# CAN-Adapter.net
KiCad netlist of a schematic drawn in EAGLE
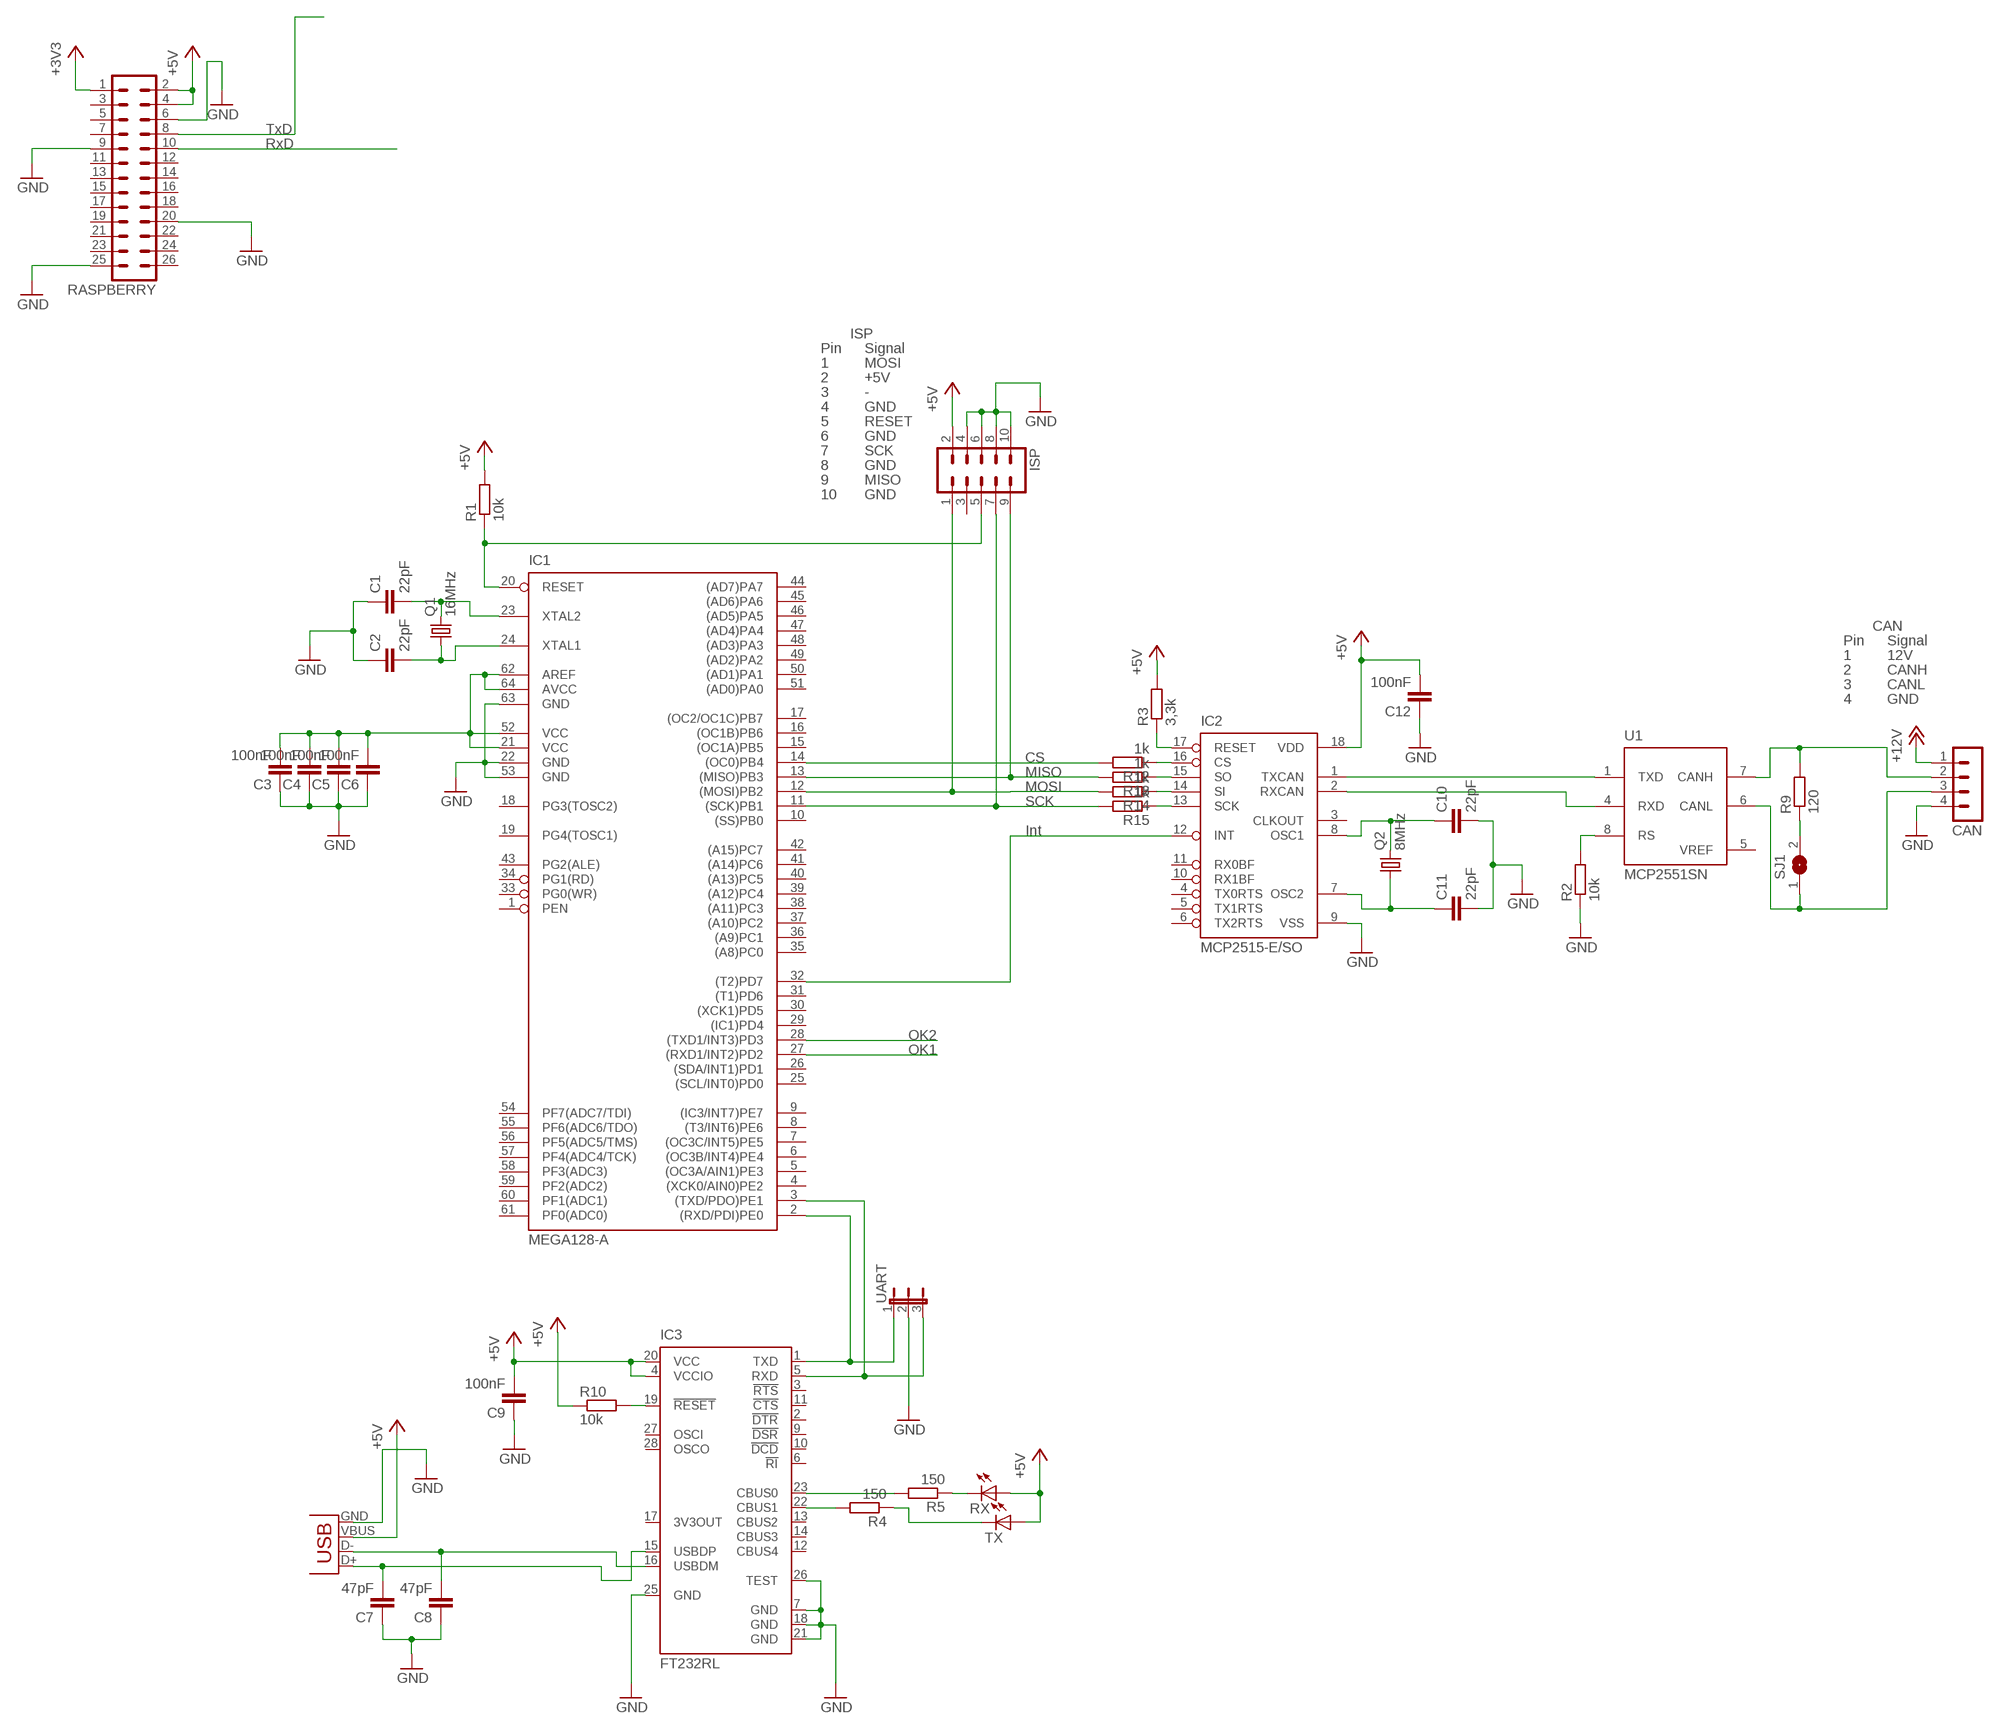
[diagram p0: schematic, sheet 1]

(export (version "E")
  (design (tool "Eeschema 10.0.6"))
  (components
    (comp (ref "C1")
      (value "22pF")
      (footprint "eagle-import:C0805")
      (libsource (lib "eagle-import") (part "C-EUC0805"))
    )
    (comp (ref "C2")
      (value "22pF")
      (footprint "eagle-import:C0805")
      (libsource (lib "eagle-import") (part "C-EUC0805"))
    )
    (comp (ref "C3")
      (value "100nF")
      (footprint "eagle-import:C0805")
      (libsource (lib "eagle-import") (part "C-EUC0805"))
    )
    (comp (ref "C4")
      (value "100nF")
      (footprint "eagle-import:C0805")
      (libsource (lib "eagle-import") (part "C-EUC0805"))
    )
    (comp (ref "C5")
      (value "100nF")
      (footprint "eagle-import:C0805")
      (libsource (lib "eagle-import") (part "C-EUC0805"))
    )
    (comp (ref "C6")
      (value "100nF")
      (footprint "eagle-import:C0805")
      (libsource (lib "eagle-import") (part "C-EUC0805"))
    )
    (comp (ref "C7")
      (value "47pF")
      (footprint "eagle-import:C0805")
      (libsource (lib "eagle-import") (part "C-EUC0805"))
    )
    (comp (ref "C8")
      (value "47pF")
      (footprint "eagle-import:C0805")
      (libsource (lib "eagle-import") (part "C-EUC0805"))
    )
    (comp (ref "C9")
      (value "100nF")
      (footprint "eagle-import:C0805")
      (libsource (lib "eagle-import") (part "C-EUC0805"))
    )
    (comp (ref "C10")
      (value "22pF")
      (footprint "eagle-import:C0805")
      (libsource (lib "eagle-import") (part "C-EUC0805"))
    )
    (comp (ref "C11")
      (value "22pF")
      (footprint "eagle-import:C0805")
      (libsource (lib "eagle-import") (part "C-EUC0805"))
    )
    (comp (ref "C12")
      (value "100nF")
      (footprint "eagle-import:C0805")
      (libsource (lib "eagle-import") (part "C-EUC0805"))
    )
    (comp (ref "CAN")
      (value "MA04-1")
      (footprint "eagle-import:MA04-1")
      (libsource (lib "eagle-import") (part "MA04-1"))
    )
    (comp (ref "IC1")
      (value "MEGA128-A")
      (footprint "eagle-import:TQFP64")
      (fields (field (name "MPN") "ATMEGA128-16AU"))
      (libsource (lib "eagle-import") (part "MEGA128-A"))
    )
    (comp (ref "IC2")
      (value "MCP2515-E/SO")
      (footprint "eagle-import:SO18L")
      (libsource (lib "eagle-import") (part "MCP2515-E/SO"))
    )
    (comp (ref "IC3")
      (value "FT232RL")
      (footprint "eagle-import:SSOP28")
      (libsource (lib "eagle-import") (part "FT232RL"))
    )
    (comp (ref "ISP")
      (value "ML10")
      (footprint "eagle-import:ML10")
      (libsource (lib "eagle-import") (part "ML10"))
    )
    (comp (ref "Q1")
      (value "16MHz")
      (footprint "eagle-import:CSM-7X-DU")
      (libsource (lib "eagle-import") (part "CSM-7X-DU"))
    )
    (comp (ref "Q2")
      (value "8MHz")
      (footprint "eagle-import:HC49UP")
      (libsource (lib "eagle-import") (part "CRYSTALHC49UP"))
    )
    (comp (ref "R1")
      (value "10k")
      (footprint "eagle-import:R0805")
      (libsource (lib "eagle-import") (part "R-EU_R0805"))
    )
    (comp (ref "R2")
      (value "10k")
      (footprint "eagle-import:M0805")
      (libsource (lib "eagle-import") (part "R-EU_M0805"))
    )
    (comp (ref "R3")
      (value "3,3k")
      (footprint "eagle-import:M0805")
      (libsource (lib "eagle-import") (part "R-EU_M0805"))
    )
    (comp (ref "R4")
      (value "150")
      (footprint "eagle-import:M0805")
      (libsource (lib "eagle-import") (part "R-EU_M0805"))
    )
    (comp (ref "R5")
      (value "150")
      (footprint "eagle-import:M0805")
      (libsource (lib "eagle-import") (part "R-EU_M0805"))
    )
    (comp (ref "R9")
      (value "120")
      (footprint "eagle-import:M0805")
      (libsource (lib "eagle-import") (part "R-EU_M0805"))
    )
    (comp (ref "R10")
      (value "10k")
      (footprint "eagle-import:M0805")
      (libsource (lib "eagle-import") (part "R-EU_M0805"))
    )
    (comp (ref "R12")
      (value "1k")
      (footprint "eagle-import:R0402")
      (libsource (lib "eagle-import") (part "R-EU_R0402"))
    )
    (comp (ref "R13")
      (value "1k")
      (footprint "eagle-import:R0402")
      (libsource (lib "eagle-import") (part "R-EU_R0402"))
    )
    (comp (ref "R14")
      (value "1k")
      (footprint "eagle-import:R0402")
      (libsource (lib "eagle-import") (part "R-EU_R0402"))
    )
    (comp (ref "R15")
      (value "1k")
      (footprint "eagle-import:R0402")
      (libsource (lib "eagle-import") (part "R-EU_R0402"))
    )
    (comp (ref "RASPBERRY")
      (value "MA13-2")
      (footprint "eagle-import:MA13-2")
      (libsource (lib "eagle-import") (part "MA13-2"))
    )
    (comp (ref "RX")
      (value "LEDCHIP-LED0805")
      (footprint "eagle-import:CHIP-LED0805")
      (libsource (lib "eagle-import") (part "LEDCHIP-LED0805"))
    )
    (comp (ref "SJ1") (value "SJ") (footprint "eagle-import:SJ") (libsource (lib "eagle-import") (part "SJ")))
    (comp (ref "TX")
      (value "LEDCHIP-LED0805")
      (footprint "eagle-import:CHIP-LED0805")
      (libsource (lib "eagle-import") (part "LEDCHIP-LED0805"))
    )
    (comp (ref "U1")
      (value "MCP2551SN")
      (footprint "eagle-import:SO-08")
      (libsource (lib "eagle-import") (part "MCP2551SN"))
    )
    (comp (ref "UART")
      (value "JP2E")
      (footprint "eagle-import:JP2")
      (libsource (lib "eagle-import") (part "JP2E"))
    )
    (comp (ref "X1")
      (value "USB-B-H")
      (footprint "eagle-import:USB-B-H")
      (libsource (lib "eagle-import") (part "USB-B-H"))
    )
  )
  (nets
    (net (code "1") (name "+3V3") (class "Default")
      (node (ref "RASPBERRY") (pin "1") (pinfunction "1_1") (pintype "passive"))
    )
    (net (code "2") (name "+5V") (class "Default")
      (node (ref "C12") (pin "2") (pinfunction "2_2") (pintype "passive"))
      (node (ref "C9") (pin "2") (pinfunction "2_2") (pintype "passive"))
      (node (ref "IC2") (pin "18") (pinfunction "VDD_18") (pintype "power_in"))
      (node (ref "IC3") (pin "20") (pinfunction "VCC_20") (pintype "power_in"))
      (node (ref "IC3") (pin "4") (pinfunction "VCCIO_4") (pintype "power_in"))
      (node (ref "ISP") (pin "2") (pinfunction "2_2") (pintype "passive"))
      (node (ref "R1") (pin "2") (pinfunction "2_2") (pintype "passive"))
      (node (ref "R10") (pin "1") (pinfunction "1_1") (pintype "passive"))
      (node (ref "R3") (pin "2") (pinfunction "2_2") (pintype "passive"))
      (node (ref "RASPBERRY") (pin "2") (pinfunction "2_2") (pintype "passive"))
      (node (ref "RASPBERRY") (pin "4") (pinfunction "4_4") (pintype "passive"))
      (node (ref "RX") (pin "A") (pinfunction "A_A") (pintype "passive"))
      (node (ref "TX") (pin "A") (pinfunction "A_A") (pintype "passive"))
      (node (ref "X1") (pin "VBUS") (pinfunction "VBUS_VBUS") (pintype "bidirectional"))
    )
    (net (code "3") (name "+12V") (class "Default")
      (node (ref "CAN") (pin "1") (pinfunction "1_1") (pintype "passive"))
    )
    (net (code "4") (name "/VREF") (class "Default")
      (node (ref "U1") (pin "5") (pinfunction "VREF_5") (pintype "power_in"))
    )
    (net (code "5") (name "GND") (class "Default")
      (node (ref "C1") (pin "1") (pinfunction "1_1") (pintype "passive"))
      (node (ref "C10") (pin "2") (pinfunction "2_2") (pintype "passive"))
      (node (ref "C11") (pin "2") (pinfunction "2_2") (pintype "passive"))
      (node (ref "C12") (pin "1") (pinfunction "1_1") (pintype "passive"))
      (node (ref "C2") (pin "1") (pinfunction "1_1") (pintype "passive"))
      (node (ref "C3") (pin "1") (pinfunction "1_1") (pintype "passive"))
      (node (ref "C4") (pin "1") (pinfunction "1_1") (pintype "passive"))
      (node (ref "C5") (pin "1") (pinfunction "1_1") (pintype "passive"))
      (node (ref "C6") (pin "1") (pinfunction "1_1") (pintype "passive"))
      (node (ref "C7") (pin "1") (pinfunction "1_1") (pintype "passive"))
      (node (ref "C8") (pin "1") (pinfunction "1_1") (pintype "passive"))
      (node (ref "C9") (pin "1") (pinfunction "1_1") (pintype "passive"))
      (node (ref "CAN") (pin "4") (pinfunction "4_4") (pintype "passive"))
      (node (ref "IC1") (pin "22") (pinfunction "GND_22") (pintype "power_in"))
      (node (ref "IC1") (pin "53") (pinfunction "GND_53") (pintype "power_in"))
      (node (ref "IC1") (pin "63") (pinfunction "GND_63") (pintype "power_in"))
      (node (ref "IC2") (pin "9") (pinfunction "VSS_9") (pintype "power_in"))
      (node (ref "IC3") (pin "18") (pinfunction "GND_18") (pintype "power_in"))
      (node (ref "IC3") (pin "21") (pinfunction "GND_21") (pintype "power_in"))
      (node (ref "IC3") (pin "25") (pinfunction "GND_25") (pintype "power_in"))
      (node (ref "IC3") (pin "26") (pinfunction "TEST_26") (pintype "input"))
      (node (ref "IC3") (pin "7") (pinfunction "GND_7") (pintype "power_in"))
      (node (ref "ISP") (pin "10") (pinfunction "10_10") (pintype "passive"))
      (node (ref "ISP") (pin "4") (pinfunction "4_4") (pintype "passive"))
      (node (ref "ISP") (pin "6") (pinfunction "6_6") (pintype "passive"))
      (node (ref "ISP") (pin "8") (pinfunction "8_8") (pintype "passive"))
      (node (ref "R2") (pin "1") (pinfunction "1_1") (pintype "passive"))
      (node (ref "RASPBERRY") (pin "20") (pinfunction "20_20") (pintype "passive"))
      (node (ref "RASPBERRY") (pin "25") (pinfunction "25_25") (pintype "passive"))
      (node (ref "RASPBERRY") (pin "6") (pinfunction "6_6") (pintype "passive"))
      (node (ref "RASPBERRY") (pin "9") (pinfunction "9_9") (pintype "passive"))
      (node (ref "UART") (pin "2") (pinfunction "2_2") (pintype "passive"))
      (node (ref "X1") (pin "GND") (pinfunction "GND_GND") (pintype "bidirectional"))
    )
    (net (code "6") (name "Net-(IC1-(MISO)PB3)") (class "Default")
      (node (ref "IC1") (pin "13") (pinfunction "(MISO)PB3_13") (pintype "bidirectional"))
      (node (ref "ISP") (pin "9") (pinfunction "9_9") (pintype "passive"))
      (node (ref "R13") (pin "2") (pinfunction "2_2") (pintype "passive"))
    )
    (net (code "7") (name "Net-(IC1-(MOSI)PB2)") (class "Default")
      (node (ref "IC1") (pin "12") (pinfunction "(MOSI)PB2_12") (pintype "bidirectional"))
      (node (ref "ISP") (pin "1") (pinfunction "1_1") (pintype "passive"))
      (node (ref "R14") (pin "2") (pinfunction "2_2") (pintype "passive"))
    )
    (net (code "8") (name "Net-(IC1-(OC0)PB4)") (class "Default")
      (node (ref "IC1") (pin "14") (pinfunction "(OC0)PB4_14") (pintype "bidirectional"))
      (node (ref "R12") (pin "2") (pinfunction "2_2") (pintype "passive"))
    )
    (net (code "9") (name "Net-(IC1-(RXD{slash}PDI)PE0)") (class "Default")
      (node (ref "IC1") (pin "2") (pinfunction "(RXD/PDI)PE0_2") (pintype "bidirectional"))
      (node (ref "IC3") (pin "1") (pinfunction "TXD_1") (pintype "output"))
      (node (ref "UART") (pin "1") (pinfunction "1_1") (pintype "passive"))
    )
    (net (code "10") (name "Net-(IC1-(SCK)PB1)") (class "Default")
      (node (ref "IC1") (pin "11") (pinfunction "(SCK)PB1_11") (pintype "bidirectional"))
      (node (ref "ISP") (pin "7") (pinfunction "7_7") (pintype "passive"))
      (node (ref "R15") (pin "2") (pinfunction "2_2") (pintype "passive"))
    )
    (net (code "11") (name "Net-(IC1-(T2)PD7)") (class "Default")
      (node (ref "IC1") (pin "32") (pinfunction "(T2)PD7_32") (pintype "bidirectional"))
      (node (ref "IC2") (pin "12") (pinfunction "INT_12") (pintype "output"))
    )
    (net (code "12") (name "Net-(IC1-(TXD{slash}PDO)PE1)") (class "Default")
      (node (ref "IC1") (pin "3") (pinfunction "(TXD/PDO)PE1_3") (pintype "bidirectional"))
      (node (ref "IC3") (pin "5") (pinfunction "RXD_5") (pintype "input"))
      (node (ref "UART") (pin "3") (pinfunction "3_3") (pintype "passive"))
    )
    (net (code "13") (name "Net-(IC1-AREF)") (class "Default")
      (node (ref "C3") (pin "2") (pinfunction "2_2") (pintype "passive"))
      (node (ref "C4") (pin "2") (pinfunction "2_2") (pintype "passive"))
      (node (ref "C5") (pin "2") (pinfunction "2_2") (pintype "passive"))
      (node (ref "C6") (pin "2") (pinfunction "2_2") (pintype "passive"))
      (node (ref "IC1") (pin "21") (pinfunction "VCC_21") (pintype "power_in"))
      (node (ref "IC1") (pin "52") (pinfunction "VCC_52") (pintype "power_in"))
      (node (ref "IC1") (pin "62") (pinfunction "AREF_62") (pintype "passive"))
      (node (ref "IC1") (pin "64") (pinfunction "AVCC_64") (pintype "power_in"))
    )
    (net (code "14") (name "Net-(IC1-RESET)") (class "Default")
      (node (ref "IC1") (pin "20") (pinfunction "RESET_20") (pintype "input"))
      (node (ref "ISP") (pin "5") (pinfunction "5_5") (pintype "passive"))
      (node (ref "R1") (pin "1") (pinfunction "1_1") (pintype "passive"))
    )
    (net (code "15") (name "Net-(IC1-XTAL1)") (class "Default")
      (node (ref "C2") (pin "2") (pinfunction "2_2") (pintype "passive"))
      (node (ref "IC1") (pin "24") (pinfunction "XTAL1_24") (pintype "bidirectional"))
      (node (ref "Q1") (pin "1") (pinfunction "1_1") (pintype "passive"))
    )
    (net (code "16") (name "Net-(IC1-XTAL2)") (class "Default")
      (node (ref "C1") (pin "2") (pinfunction "2_2") (pintype "passive"))
      (node (ref "IC1") (pin "23") (pinfunction "XTAL2_23") (pintype "bidirectional"))
      (node (ref "Q1") (pin "2") (pinfunction "2_2") (pintype "passive"))
    )
    (net (code "17") (name "Net-(IC2-CS)") (class "Default")
      (node (ref "IC2") (pin "16") (pinfunction "CS_16") (pintype "input"))
      (node (ref "R12") (pin "1") (pinfunction "1_1") (pintype "passive"))
    )
    (net (code "18") (name "Net-(IC2-OSC1)") (class "Default")
      (node (ref "C10") (pin "1") (pinfunction "1_1") (pintype "passive"))
      (node (ref "IC2") (pin "8") (pinfunction "OSC1_8") (pintype "input"))
      (node (ref "Q2") (pin "2") (pinfunction "2_2") (pintype "passive"))
    )
    (net (code "19") (name "Net-(IC2-OSC2)") (class "Default")
      (node (ref "C11") (pin "1") (pinfunction "1_1") (pintype "passive"))
      (node (ref "IC2") (pin "7") (pinfunction "OSC2_7") (pintype "output"))
      (node (ref "Q2") (pin "1") (pinfunction "1_1") (pintype "passive"))
    )
    (net (code "20") (name "Net-(IC2-RESET)") (class "Default")
      (node (ref "IC2") (pin "17") (pinfunction "RESET_17") (pintype "input"))
      (node (ref "R3") (pin "1") (pinfunction "1_1") (pintype "passive"))
    )
    (net (code "21") (name "Net-(IC2-RXCAN)") (class "Default")
      (node (ref "IC2") (pin "2") (pinfunction "RXCAN_2") (pintype "input"))
      (node (ref "U1") (pin "4") (pinfunction "RXD_4") (pintype "output"))
    )
    (net (code "22") (name "Net-(IC2-SCK)") (class "Default")
      (node (ref "IC2") (pin "13") (pinfunction "SCK_13") (pintype "input"))
      (node (ref "R15") (pin "1") (pinfunction "1_1") (pintype "passive"))
    )
    (net (code "23") (name "Net-(IC2-SI)") (class "Default")
      (node (ref "IC2") (pin "14") (pinfunction "SI_14") (pintype "input"))
      (node (ref "R14") (pin "1") (pinfunction "1_1") (pintype "passive"))
    )
    (net (code "24") (name "Net-(IC2-SO)") (class "Default")
      (node (ref "IC2") (pin "15") (pinfunction "SO_15") (pintype "output"))
      (node (ref "R13") (pin "1") (pinfunction "1_1") (pintype "passive"))
    )
    (net (code "25") (name "Net-(IC2-TXCAN)") (class "Default")
      (node (ref "IC2") (pin "1") (pinfunction "TXCAN_1") (pintype "output"))
      (node (ref "U1") (pin "1") (pinfunction "TXD_1") (pintype "input"))
    )
    (net (code "26") (name "Net-(IC3-CBUS0)") (class "Default")
      (node (ref "IC3") (pin "23") (pinfunction "CBUS0_23") (pintype "bidirectional"))
      (node (ref "R5") (pin "2") (pinfunction "2_2") (pintype "passive"))
    )
    (net (code "27") (name "Net-(IC3-CBUS1)") (class "Default")
      (node (ref "IC3") (pin "22") (pinfunction "CBUS1_22") (pintype "bidirectional"))
      (node (ref "R4") (pin "2") (pinfunction "2_2") (pintype "passive"))
    )
    (net (code "28") (name "Net-(IC3-USBDM)") (class "Default")
      (node (ref "C8") (pin "2") (pinfunction "2_2") (pintype "passive"))
      (node (ref "IC3") (pin "16") (pinfunction "USBDM_16") (pintype "bidirectional"))
      (node (ref "X1") (pin "D-") (pinfunction "D-_D-") (pintype "bidirectional"))
    )
    (net (code "29") (name "Net-(IC3-USBDP)") (class "Default")
      (node (ref "C7") (pin "2") (pinfunction "2_2") (pintype "passive"))
      (node (ref "IC3") (pin "15") (pinfunction "USBDP_15") (pintype "bidirectional"))
      (node (ref "X1") (pin "D+") (pinfunction "D+_D+") (pintype "bidirectional"))
    )
    (net (code "30") (name "Net-(IC3-~{RESET})") (class "Default")
      (node (ref "IC3") (pin "19") (pinfunction "~{RESET}_19") (pintype "input"))
      (node (ref "R10") (pin "2") (pinfunction "2_2") (pintype "passive"))
    )
    (net (code "31") (name "Net-(R4-Pad1)") (class "Default")
      (node (ref "R4") (pin "1") (pinfunction "1_1") (pintype "passive"))
      (node (ref "TX") (pin "C") (pinfunction "C_C") (pintype "passive"))
    )
    (net (code "32") (name "Net-(R5-Pad1)") (class "Default")
      (node (ref "R5") (pin "1") (pinfunction "1_1") (pintype "passive"))
      (node (ref "RX") (pin "C") (pinfunction "C_C") (pintype "passive"))
    )
    (net (code "33") (name "Net-(R9-Pad1)") (class "Default")
      (node (ref "R9") (pin "1") (pinfunction "1_1") (pintype "passive"))
      (node (ref "SJ1") (pin "2") (pinfunction "2_2") (pintype "passive"))
    )
    (net (code "34") (name "Net-(U1A-CANH)") (class "Default")
      (node (ref "CAN") (pin "2") (pinfunction "2_2") (pintype "passive"))
      (node (ref "R9") (pin "2") (pinfunction "2_2") (pintype "passive"))
      (node (ref "U1") (pin "7") (pinfunction "CANH_7") (pintype "bidirectional"))
    )
    (net (code "35") (name "Net-(U1A-CANL)") (class "Default")
      (node (ref "CAN") (pin "3") (pinfunction "3_3") (pintype "passive"))
      (node (ref "SJ1") (pin "1") (pinfunction "1_1") (pintype "passive"))
      (node (ref "U1") (pin "6") (pinfunction "CANL_6") (pintype "bidirectional"))
    )
    (net (code "36") (name "Net-(U1A-RS)") (class "Default")
      (node (ref "R2") (pin "2") (pinfunction "2_2") (pintype "passive"))
      (node (ref "U1") (pin "8") (pinfunction "RS_8") (pintype "input"))
    )
    (net (code "37") (name "unconnected-(IC1-(A8)PC0-Pad35)") (class "Default")
      (node (ref "IC1") (pin "35") (pinfunction "(A8)PC0_35") (pintype "output"))
    )
    (net (code "38") (name "unconnected-(IC1-(A9)PC1-Pad36)") (class "Default")
      (node (ref "IC1") (pin "36") (pinfunction "(A9)PC1_36") (pintype "output"))
    )
    (net (code "39") (name "unconnected-(IC1-(A10)PC2-Pad37)") (class "Default")
      (node (ref "IC1") (pin "37") (pinfunction "(A10)PC2_37") (pintype "output"))
    )
    (net (code "40") (name "unconnected-(IC1-(A11)PC3-Pad38)") (class "Default")
      (node (ref "IC1") (pin "38") (pinfunction "(A11)PC3_38") (pintype "output"))
    )
    (net (code "41") (name "unconnected-(IC1-(A12)PC4-Pad39)") (class "Default")
      (node (ref "IC1") (pin "39") (pinfunction "(A12)PC4_39") (pintype "output"))
    )
    (net (code "42") (name "unconnected-(IC1-(A13)PC5-Pad40)") (class "Default")
      (node (ref "IC1") (pin "40") (pinfunction "(A13)PC5_40") (pintype "output"))
    )
    (net (code "43") (name "unconnected-(IC1-(A14)PC6-Pad41)") (class "Default")
      (node (ref "IC1") (pin "41") (pinfunction "(A14)PC6_41") (pintype "output"))
    )
    (net (code "44") (name "unconnected-(IC1-(A15)PC7-Pad42)") (class "Default")
      (node (ref "IC1") (pin "42") (pinfunction "(A15)PC7_42") (pintype "output"))
    )
    (net (code "45") (name "unconnected-(IC1-(AD0)PA0-Pad51)") (class "Default")
      (node (ref "IC1") (pin "51") (pinfunction "(AD0)PA0_51") (pintype "bidirectional"))
    )
    (net (code "46") (name "unconnected-(IC1-(AD1)PA1-Pad50)") (class "Default")
      (node (ref "IC1") (pin "50") (pinfunction "(AD1)PA1_50") (pintype "bidirectional"))
    )
    (net (code "47") (name "unconnected-(IC1-(AD2)PA2-Pad49)") (class "Default")
      (node (ref "IC1") (pin "49") (pinfunction "(AD2)PA2_49") (pintype "bidirectional"))
    )
    (net (code "48") (name "unconnected-(IC1-(AD3)PA3-Pad48)") (class "Default")
      (node (ref "IC1") (pin "48") (pinfunction "(AD3)PA3_48") (pintype "bidirectional"))
    )
    (net (code "49") (name "unconnected-(IC1-(AD4)PA4-Pad47)") (class "Default")
      (node (ref "IC1") (pin "47") (pinfunction "(AD4)PA4_47") (pintype "bidirectional"))
    )
    (net (code "50") (name "unconnected-(IC1-(AD5)PA5-Pad46)") (class "Default")
      (node (ref "IC1") (pin "46") (pinfunction "(AD5)PA5_46") (pintype "bidirectional"))
    )
    (net (code "51") (name "unconnected-(IC1-(AD6)PA6-Pad45)") (class "Default")
      (node (ref "IC1") (pin "45") (pinfunction "(AD6)PA6_45") (pintype "bidirectional"))
    )
    (net (code "52") (name "unconnected-(IC1-(AD7)PA7-Pad44)") (class "Default")
      (node (ref "IC1") (pin "44") (pinfunction "(AD7)PA7_44") (pintype "bidirectional"))
    )
    (net (code "53") (name "unconnected-(IC1-(IC1)PD4-Pad29)") (class "Default")
      (node (ref "IC1") (pin "29") (pinfunction "(IC1)PD4_29") (pintype "bidirectional"))
    )
    (net (code "54") (name "unconnected-(IC1-(IC3{slash}INT7)PE7-Pad9)") (class "Default")
      (node (ref "IC1") (pin "9") (pinfunction "(IC3/INT7)PE7_9") (pintype "bidirectional"))
    )
    (net (code "55") (name "unconnected-(IC1-(OC1A)PB5-Pad15)") (class "Default")
      (node (ref "IC1") (pin "15") (pinfunction "(OC1A)PB5_15") (pintype "bidirectional"))
    )
    (net (code "56") (name "unconnected-(IC1-(OC1B)PB6-Pad16)") (class "Default")
      (node (ref "IC1") (pin "16") (pinfunction "(OC1B)PB6_16") (pintype "bidirectional"))
    )
    (net (code "57") (name "unconnected-(IC1-(OC2{slash}OC1C)PB7-Pad17)") (class "Default")
      (node (ref "IC1") (pin "17") (pinfunction "(OC2/OC1C)PB7_17") (pintype "bidirectional"))
    )
    (net (code "58") (name "unconnected-(IC1-(OC3A{slash}AIN1)PE3-Pad5)") (class "Default")
      (node (ref "IC1") (pin "5") (pinfunction "(OC3A/AIN1)PE3_5") (pintype "bidirectional"))
    )
    (net (code "59") (name "unconnected-(IC1-(OC3B{slash}INT4)PE4-Pad6)") (class "Default")
      (node (ref "IC1") (pin "6") (pinfunction "(OC3B/INT4)PE4_6") (pintype "bidirectional"))
    )
    (net (code "60") (name "unconnected-(IC1-(OC3C{slash}INT5)PE5-Pad7)") (class "Default")
      (node (ref "IC1") (pin "7") (pinfunction "(OC3C/INT5)PE5_7") (pintype "bidirectional"))
    )
    (net (code "61") (name "unconnected-(IC1-(RXD1{slash}INT2)PD2-Pad27)") (class "Default")
      (node (ref "IC1") (pin "27") (pinfunction "(RXD1/INT2)PD2_27") (pintype "bidirectional"))
    )
    (net (code "62") (name "unconnected-(IC1-(SCL{slash}INT0)PD0-Pad25)") (class "Default")
      (node (ref "IC1") (pin "25") (pinfunction "(SCL/INT0)PD0_25") (pintype "bidirectional"))
    )
    (net (code "63") (name "unconnected-(IC1-(SDA{slash}INT1)PD1-Pad26)") (class "Default")
      (node (ref "IC1") (pin "26") (pinfunction "(SDA/INT1)PD1_26") (pintype "bidirectional"))
    )
    (net (code "64") (name "unconnected-(IC1-(SS)PB0-Pad10)") (class "Default")
      (node (ref "IC1") (pin "10") (pinfunction "(SS)PB0_10") (pintype "bidirectional"))
    )
    (net (code "65") (name "unconnected-(IC1-(T1)PD6-Pad31)") (class "Default")
      (node (ref "IC1") (pin "31") (pinfunction "(T1)PD6_31") (pintype "bidirectional"))
    )
    (net (code "66") (name "unconnected-(IC1-(T3{slash}INT6)PE6-Pad8)") (class "Default")
      (node (ref "IC1") (pin "8") (pinfunction "(T3/INT6)PE6_8") (pintype "bidirectional"))
    )
    (net (code "67") (name "unconnected-(IC1-(TXD1{slash}INT3)PD3-Pad28)") (class "Default")
      (node (ref "IC1") (pin "28") (pinfunction "(TXD1/INT3)PD3_28") (pintype "bidirectional"))
    )
    (net (code "68") (name "unconnected-(IC1-(XCK0{slash}AIN0)PE2-Pad4)") (class "Default")
      (node (ref "IC1") (pin "4") (pinfunction "(XCK0/AIN0)PE2_4") (pintype "bidirectional"))
    )
    (net (code "69") (name "unconnected-(IC1-(XCK1)PD5-Pad30)") (class "Default")
      (node (ref "IC1") (pin "30") (pinfunction "(XCK1)PD5_30") (pintype "bidirectional"))
    )
    (net (code "70") (name "unconnected-(IC1-PEN-Pad1)") (class "Default")
      (node (ref "IC1") (pin "1") (pinfunction "PEN_1") (pintype "input"))
    )
    (net (code "71") (name "unconnected-(IC1-PF0(ADC0)-Pad61)") (class "Default")
      (node (ref "IC1") (pin "61") (pinfunction "PF0(ADC0)_61") (pintype "input"))
    )
    (net (code "72") (name "unconnected-(IC1-PF1(ADC1)-Pad60)") (class "Default")
      (node (ref "IC1") (pin "60") (pinfunction "PF1(ADC1)_60") (pintype "input"))
    )
    (net (code "73") (name "unconnected-(IC1-PF2(ADC2)-Pad59)") (class "Default")
      (node (ref "IC1") (pin "59") (pinfunction "PF2(ADC2)_59") (pintype "input"))
    )
    (net (code "74") (name "unconnected-(IC1-PF3(ADC3)-Pad58)") (class "Default")
      (node (ref "IC1") (pin "58") (pinfunction "PF3(ADC3)_58") (pintype "input"))
    )
    (net (code "75") (name "unconnected-(IC1-PF4(ADC4{slash}TCK)-Pad57)") (class "Default")
      (node (ref "IC1") (pin "57") (pinfunction "PF4(ADC4/TCK)_57") (pintype "input"))
    )
    (net (code "76") (name "unconnected-(IC1-PF5(ADC5{slash}TMS)-Pad56)") (class "Default")
      (node (ref "IC1") (pin "56") (pinfunction "PF5(ADC5/TMS)_56") (pintype "input"))
    )
    (net (code "77") (name "unconnected-(IC1-PF6(ADC6{slash}TDO)-Pad55)") (class "Default")
      (node (ref "IC1") (pin "55") (pinfunction "PF6(ADC6/TDO)_55") (pintype "input"))
    )
    (net (code "78") (name "unconnected-(IC1-PF7(ADC7{slash}TDI)-Pad54)") (class "Default")
      (node (ref "IC1") (pin "54") (pinfunction "PF7(ADC7/TDI)_54") (pintype "input"))
    )
    (net (code "79") (name "unconnected-(IC1-PG0(WR)-Pad33)") (class "Default")
      (node (ref "IC1") (pin "33") (pinfunction "PG0(WR)_33") (pintype "bidirectional"))
    )
    (net (code "80") (name "unconnected-(IC1-PG1(RD)-Pad34)") (class "Default")
      (node (ref "IC1") (pin "34") (pinfunction "PG1(RD)_34") (pintype "bidirectional"))
    )
    (net (code "81") (name "unconnected-(IC1-PG2(ALE)-Pad43)") (class "Default")
      (node (ref "IC1") (pin "43") (pinfunction "PG2(ALE)_43") (pintype "bidirectional"))
    )
    (net (code "82") (name "unconnected-(IC1-PG3(TOSC2)-Pad18)") (class "Default")
      (node (ref "IC1") (pin "18") (pinfunction "PG3(TOSC2)_18") (pintype "bidirectional"))
    )
    (net (code "83") (name "unconnected-(IC1-PG4(TOSC1)-Pad19)") (class "Default")
      (node (ref "IC1") (pin "19") (pinfunction "PG4(TOSC1)_19") (pintype "bidirectional"))
    )
    (net (code "84") (name "unconnected-(IC2-CLKOUT-Pad3)") (class "Default")
      (node (ref "IC2") (pin "3") (pinfunction "CLKOUT_3") (pintype "output"))
    )
    (net (code "85") (name "unconnected-(IC2-RX0BF-Pad11)") (class "Default")
      (node (ref "IC2") (pin "11") (pinfunction "RX0BF_11") (pintype "output"))
    )
    (net (code "86") (name "unconnected-(IC2-RX1BF-Pad10)") (class "Default")
      (node (ref "IC2") (pin "10") (pinfunction "RX1BF_10") (pintype "output"))
    )
    (net (code "87") (name "unconnected-(IC2-TX0RTS-Pad4)") (class "Default")
      (node (ref "IC2") (pin "4") (pinfunction "TX0RTS_4") (pintype "input"))
    )
    (net (code "88") (name "unconnected-(IC2-TX1RTS-Pad5)") (class "Default")
      (node (ref "IC2") (pin "5") (pinfunction "TX1RTS_5") (pintype "input"))
    )
    (net (code "89") (name "unconnected-(IC2-TX2RTS-Pad6)") (class "Default")
      (node (ref "IC2") (pin "6") (pinfunction "TX2RTS_6") (pintype "input"))
    )
    (net (code "90") (name "unconnected-(IC3-3V3OUT-Pad17)") (class "Default")
      (node (ref "IC3") (pin "17") (pinfunction "3V3OUT_17") (pintype "output"))
    )
    (net (code "91") (name "unconnected-(IC3-CBUS2-Pad13)") (class "Default")
      (node (ref "IC3") (pin "13") (pinfunction "CBUS2_13") (pintype "bidirectional"))
    )
    (net (code "92") (name "unconnected-(IC3-CBUS3-Pad14)") (class "Default")
      (node (ref "IC3") (pin "14") (pinfunction "CBUS3_14") (pintype "bidirectional"))
    )
    (net (code "93") (name "unconnected-(IC3-CBUS4-Pad12)") (class "Default")
      (node (ref "IC3") (pin "12") (pinfunction "CBUS4_12") (pintype "bidirectional"))
    )
    (net (code "94") (name "unconnected-(IC3-OSCI-Pad27)") (class "Default")
      (node (ref "IC3") (pin "27") (pinfunction "OSCI_27") (pintype "input"))
    )
    (net (code "95") (name "unconnected-(IC3-OSCO-Pad28)") (class "Default")
      (node (ref "IC3") (pin "28") (pinfunction "OSCO_28") (pintype "output"))
    )
    (net (code "96") (name "unconnected-(IC3-~{CTS}-Pad11)") (class "Default")
      (node (ref "IC3") (pin "11") (pinfunction "~{CTS}_11") (pintype "input"))
    )
    (net (code "97") (name "unconnected-(IC3-~{DCD}-Pad10)") (class "Default")
      (node (ref "IC3") (pin "10") (pinfunction "~{DCD}_10") (pintype "input"))
    )
    (net (code "98") (name "unconnected-(IC3-~{DSR}-Pad9)") (class "Default")
      (node (ref "IC3") (pin "9") (pinfunction "~{DSR}_9") (pintype "input"))
    )
    (net (code "99") (name "unconnected-(IC3-~{DTR}-Pad2)") (class "Default")
      (node (ref "IC3") (pin "2") (pinfunction "~{DTR}_2") (pintype "output"))
    )
    (net (code "100") (name "unconnected-(IC3-~{RI}-Pad6)") (class "Default")
      (node (ref "IC3") (pin "6") (pinfunction "~{RI}_6") (pintype "input"))
    )
    (net (code "101") (name "unconnected-(IC3-~{RTS}-Pad3)") (class "Default")
      (node (ref "IC3") (pin "3") (pinfunction "~{RTS}_3") (pintype "output"))
    )
    (net (code "102") (name "unconnected-(ISP-Pad3)") (class "Default")
      (node (ref "ISP") (pin "3") (pinfunction "3_3") (pintype "passive"))
    )
    (net (code "103") (name "unconnected-(RASPBERRY-Pad3)") (class "Default")
      (node (ref "RASPBERRY") (pin "3") (pinfunction "3_3") (pintype "passive"))
    )
    (net (code "104") (name "unconnected-(RASPBERRY-Pad5)") (class "Default")
      (node (ref "RASPBERRY") (pin "5") (pinfunction "5_5") (pintype "passive"))
    )
    (net (code "105") (name "unconnected-(RASPBERRY-Pad7)") (class "Default")
      (node (ref "RASPBERRY") (pin "7") (pinfunction "7_7") (pintype "passive"))
    )
    (net (code "106") (name "unconnected-(RASPBERRY-Pad8)") (class "Default")
      (node (ref "RASPBERRY") (pin "8") (pinfunction "8_8") (pintype "passive"))
    )
    (net (code "107") (name "unconnected-(RASPBERRY-Pad10)") (class "Default")
      (node (ref "RASPBERRY") (pin "10") (pinfunction "10_10") (pintype "passive"))
    )
    (net (code "108") (name "unconnected-(RASPBERRY-Pad11)") (class "Default")
      (node (ref "RASPBERRY") (pin "11") (pinfunction "11_11") (pintype "passive"))
    )
    (net (code "109") (name "unconnected-(RASPBERRY-Pad12)") (class "Default")
      (node (ref "RASPBERRY") (pin "12") (pinfunction "12_12") (pintype "passive"))
    )
    (net (code "110") (name "unconnected-(RASPBERRY-Pad13)") (class "Default")
      (node (ref "RASPBERRY") (pin "13") (pinfunction "13_13") (pintype "passive"))
    )
    (net (code "111") (name "unconnected-(RASPBERRY-Pad14)") (class "Default")
      (node (ref "RASPBERRY") (pin "14") (pinfunction "14_14") (pintype "passive"))
    )
    (net (code "112") (name "unconnected-(RASPBERRY-Pad15)") (class "Default")
      (node (ref "RASPBERRY") (pin "15") (pinfunction "15_15") (pintype "passive"))
    )
    (net (code "113") (name "unconnected-(RASPBERRY-Pad16)") (class "Default")
      (node (ref "RASPBERRY") (pin "16") (pinfunction "16_16") (pintype "passive"))
    )
    (net (code "114") (name "unconnected-(RASPBERRY-Pad17)") (class "Default")
      (node (ref "RASPBERRY") (pin "17") (pinfunction "17_17") (pintype "passive"))
    )
    (net (code "115") (name "unconnected-(RASPBERRY-Pad18)") (class "Default")
      (node (ref "RASPBERRY") (pin "18") (pinfunction "18_18") (pintype "passive"))
    )
    (net (code "116") (name "unconnected-(RASPBERRY-Pad19)") (class "Default")
      (node (ref "RASPBERRY") (pin "19") (pinfunction "19_19") (pintype "passive"))
    )
    (net (code "117") (name "unconnected-(RASPBERRY-Pad21)") (class "Default")
      (node (ref "RASPBERRY") (pin "21") (pinfunction "21_21") (pintype "passive"))
    )
    (net (code "118") (name "unconnected-(RASPBERRY-Pad22)") (class "Default")
      (node (ref "RASPBERRY") (pin "22") (pinfunction "22_22") (pintype "passive"))
    )
    (net (code "119") (name "unconnected-(RASPBERRY-Pad23)") (class "Default")
      (node (ref "RASPBERRY") (pin "23") (pinfunction "23_23") (pintype "passive"))
    )
    (net (code "120") (name "unconnected-(RASPBERRY-Pad24)") (class "Default")
      (node (ref "RASPBERRY") (pin "24") (pinfunction "24_24") (pintype "passive"))
    )
    (net (code "121") (name "unconnected-(RASPBERRY-Pad26)") (class "Default")
      (node (ref "RASPBERRY") (pin "26") (pinfunction "26_26") (pintype "passive"))
    )
  )
)
